# EnconderPCB.net
KiCad netlist of a schematic drawn in EAGLE
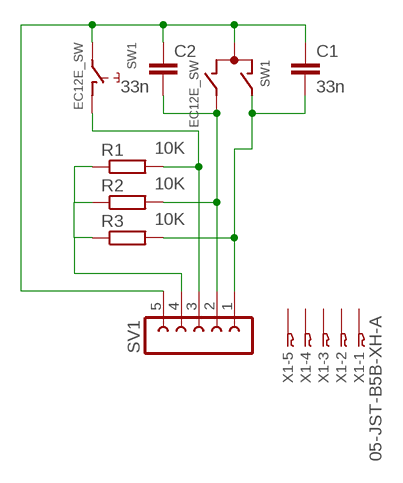
[diagram p0: schematic, sheet 1]

(export (version "E")
  (design (tool "Eeschema 10.0.6"))
  (components
    (comp (ref "C1")
      (value "33n")
      (footprint "eagle-import:C0603")
      (libsource (lib "eagle-import") (part "C-EUC0603"))
    )
    (comp (ref "C2")
      (value "33n")
      (footprint "eagle-import:C0603")
      (libsource (lib "eagle-import") (part "C-EUC0603"))
    )
    (comp (ref "R1")
      (value "10K")
      (footprint "eagle-import:R0603")
      (libsource (lib "eagle-import") (part "R-EU_R0603"))
    )
    (comp (ref "R2")
      (value "10K")
      (footprint "eagle-import:R0603")
      (libsource (lib "eagle-import") (part "R-EU_R0603"))
    )
    (comp (ref "R3")
      (value "10K")
      (footprint "eagle-import:R0603")
      (libsource (lib "eagle-import") (part "R-EU_R0603"))
    )
    (comp (ref "SV1")
      (value "FE05-1")
      (footprint "eagle-import:FE05-1")
      (libsource (lib "eagle-import") (part "FE05-1"))
    )
    (comp (ref "SW1")
      (value "EC12E_SW")
      (footprint "eagle-import:ALPS_EC12E_SW")
      (fields (field (name "MPN") "EC12E2424407"))
      (libsource (lib "eagle-import") (part "EC12E_SW"))
    )
    (comp (ref "X1")
      (value "05-JST-B5B-XH-A")
      (footprint "eagle-import:B5B-XH")
      (libsource (lib "eagle-import") (part "05-JST-B5B-XH-A"))
    )
  )
  (nets
    (net (code "1") (name "Net-(C1-Pad2)") (class "Default")
      (node (ref "C1") (pin "2") (pinfunction "2_2") (pintype "passive"))
      (node (ref "R3") (pin "2") (pinfunction "2_2") (pintype "passive"))
      (node (ref "SV1") (pin "1") (pinfunction "1_1") (pintype "passive"))
      (node (ref "SW1") (pin "A") (pinfunction "A_A") (pintype "passive"))
    )
    (net (code "2") (name "Net-(C2-Pad2)") (class "Default")
      (node (ref "C2") (pin "2") (pinfunction "2_2") (pintype "passive"))
      (node (ref "R2") (pin "2") (pinfunction "2_2") (pintype "passive"))
      (node (ref "SV1") (pin "2") (pinfunction "2_2") (pintype "passive"))
      (node (ref "SW1") (pin "B") (pinfunction "B_B") (pintype "passive"))
    )
    (net (code "3") (name "Net-(R1-Pad1)") (class "Default")
      (node (ref "R1") (pin "1") (pinfunction "1_1") (pintype "passive"))
      (node (ref "R2") (pin "1") (pinfunction "1_1") (pintype "passive"))
      (node (ref "R3") (pin "1") (pinfunction "1_1") (pintype "passive"))
      (node (ref "SV1") (pin "4") (pinfunction "4_4") (pintype "passive"))
    )
    (net (code "4") (name "Net-(SW1B-1)") (class "Default")
      (node (ref "R1") (pin "2") (pinfunction "2_2") (pintype "passive"))
      (node (ref "SV1") (pin "3") (pinfunction "3_3") (pintype "passive"))
      (node (ref "SW1") (pin "D") (pinfunction "1_D") (pintype "passive"))
    )
    (net (code "5") (name "Net-(SW1B-2)") (class "Default")
      (node (ref "C1") (pin "1") (pinfunction "1_1") (pintype "passive"))
      (node (ref "C2") (pin "1") (pinfunction "1_1") (pintype "passive"))
      (node (ref "SV1") (pin "5") (pinfunction "5_5") (pintype "passive"))
      (node (ref "SW1") (pin "C") (pinfunction "C_C") (pintype "passive"))
      (node (ref "SW1") (pin "E") (pinfunction "2_E") (pintype "passive"))
    )
    (net (code "6") (name "unconnected-(X1A-1-PadP$1)") (class "Default")
      (node (ref "X1") (pin "P$1") (pinfunction "1_P$1") (pintype "passive"))
    )
    (net (code "7") (name "unconnected-(X1B-1-PadP$2)") (class "Default")
      (node (ref "X1") (pin "P$2") (pinfunction "1_P$2") (pintype "passive"))
    )
    (net (code "8") (name "unconnected-(X1C-1-PadP$3)") (class "Default")
      (node (ref "X1") (pin "P$3") (pinfunction "1_P$3") (pintype "passive"))
    )
    (net (code "9") (name "unconnected-(X1D-1-PadP$4)") (class "Default")
      (node (ref "X1") (pin "P$4") (pinfunction "1_P$4") (pintype "passive"))
    )
    (net (code "10") (name "unconnected-(X1E-1-PadP$5)") (class "Default")
      (node (ref "X1") (pin "P$5") (pinfunction "1_P$5") (pintype "passive"))
    )
  )
)
